# Schematic.net
KiCad netlist of a schematic drawn in Altium Designer
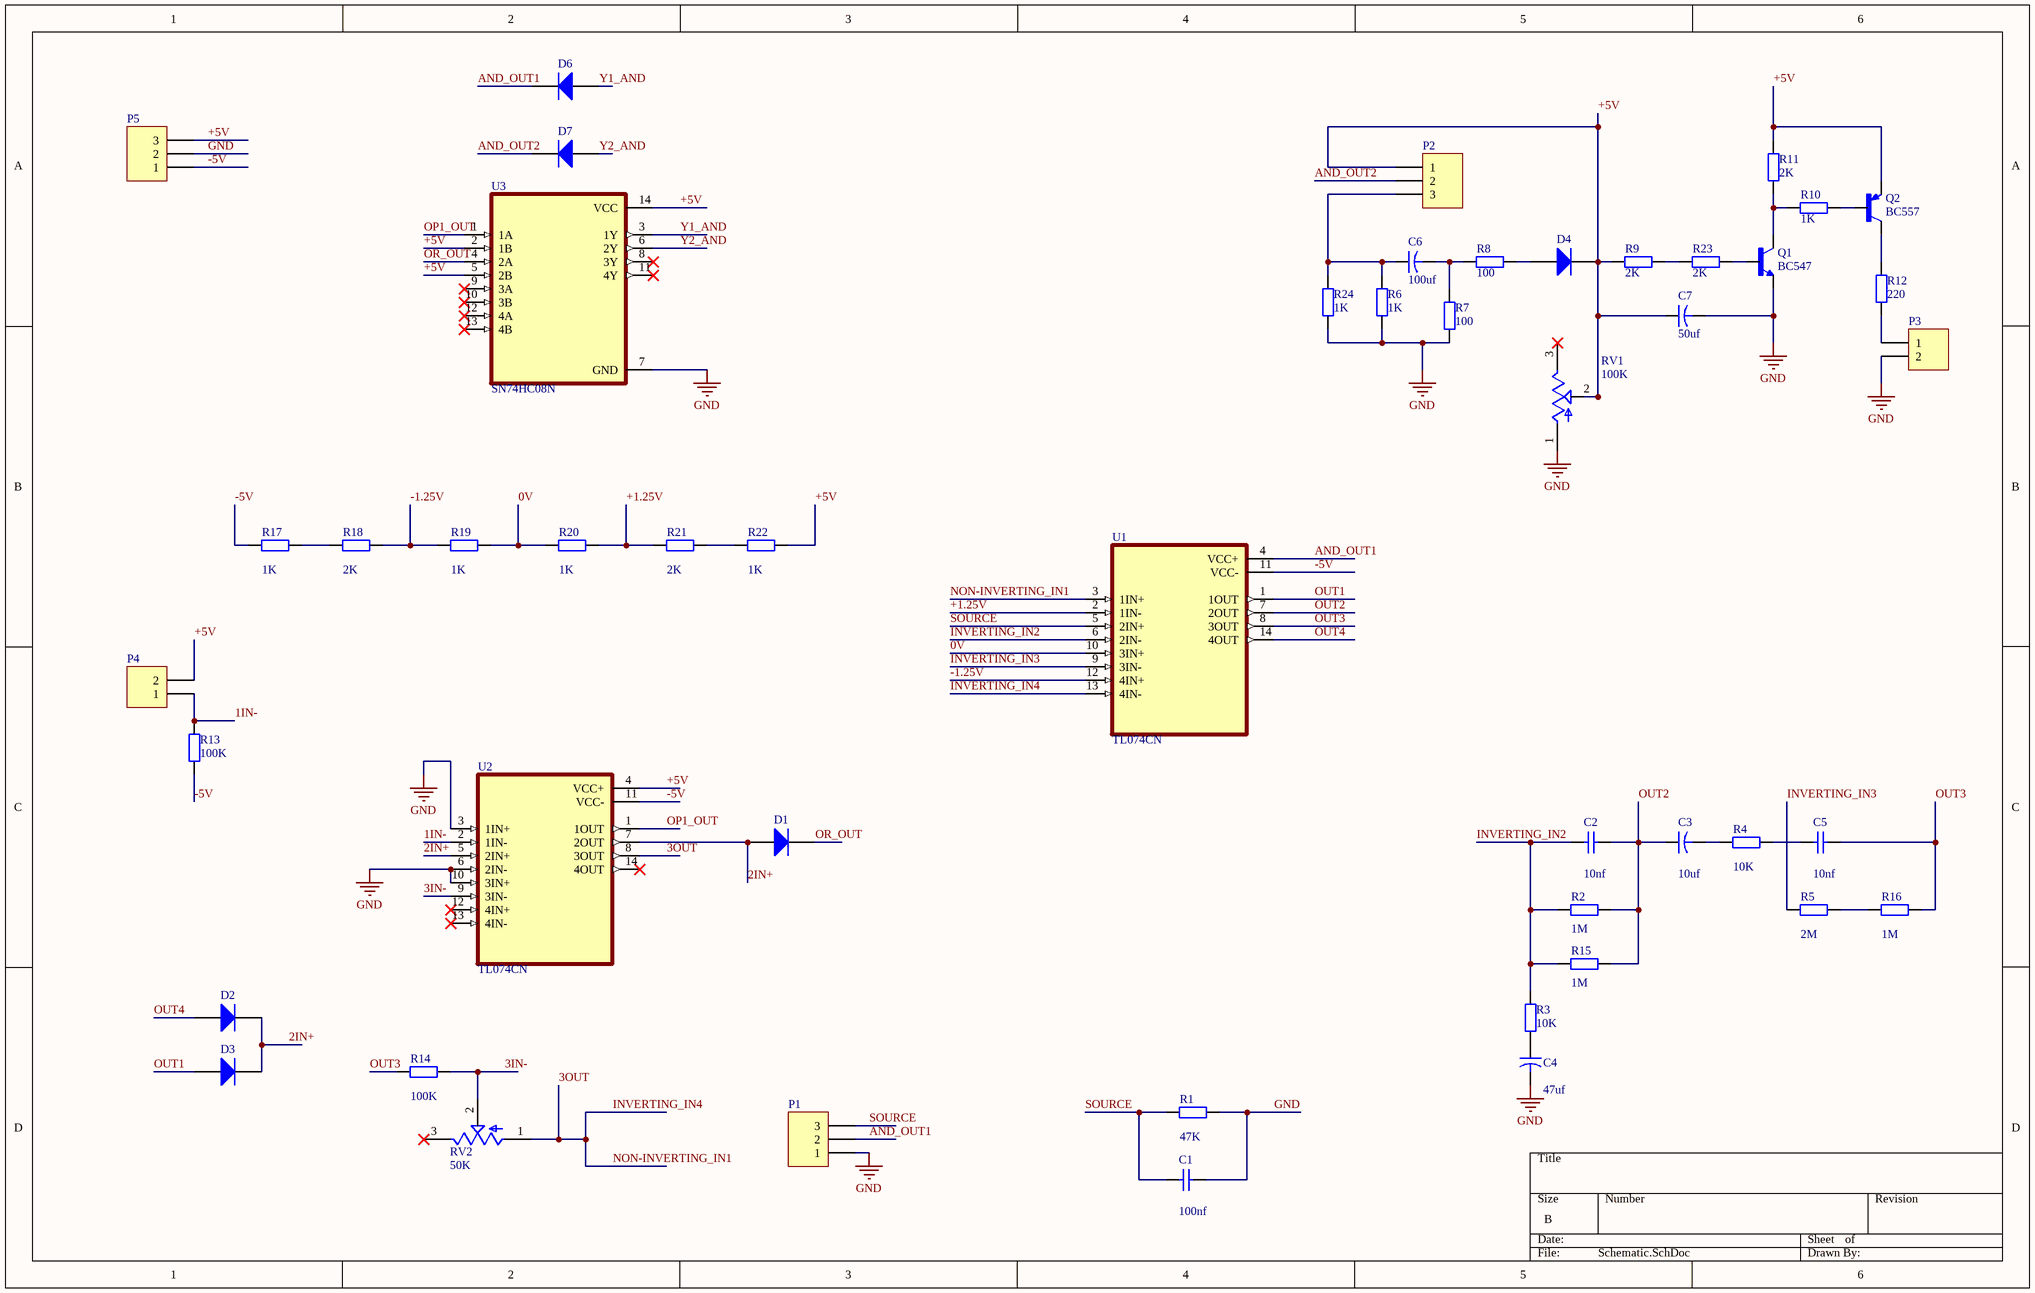
[diagram p0: Schematic.SchDoc]

(export (version "E")
  (design (tool "Eeschema 10.0.6"))
  (components
    (comp (ref "C1")
      (value "100nf")
      (footprint "RAD-0.3")
      (description "Capacitor")
      (fields (field (name "Comment") "Cap") (field (name "PUBLISHER") "Altium Limited"))
      (libsource (lib "Miscellaneous Devices") (part "Cap"))
    )
    (comp (ref "C2")
      (value "10nf")
      (footprint "RAD-0.3")
      (description "Capacitor")
      (fields (field (name "Comment") "Cap") (field (name "PUBLISHER") "Altium Limited"))
      (libsource (lib "Miscellaneous Devices") (part "Cap"))
    )
    (comp (ref "C3")
      (value "10uf")
      (footprint "CAPR5-4X5")
      (description "Capacitor")
      (fields (field (name "Comment") "Cap2") (field (name "PUBLISHER") "Altium Limited"))
      (libsource (lib "Miscellaneous Devices") (part "Cap2"))
    )
    (comp (ref "C4")
      (value "47uf")
      (footprint "CAPR5-4X5")
      (description "Capacitor")
      (fields (field (name "Comment") "Cap2") (field (name "PUBLISHER") "Altium Limited"))
      (libsource (lib "Miscellaneous Devices") (part "Cap2"))
    )
    (comp (ref "C5")
      (value "10nf")
      (footprint "RAD-0.3")
      (description "Capacitor")
      (fields (field (name "Comment") "Cap") (field (name "PUBLISHER") "Altium Limited"))
      (libsource (lib "Miscellaneous Devices") (part "Cap"))
    )
    (comp (ref "C6")
      (value "100uf")
      (footprint "CAPR5-4X5")
      (description "Capacitor")
      (fields (field (name "Comment") "Cap2") (field (name "PUBLISHER") "Altium Limited"))
      (libsource (lib "Miscellaneous Devices") (part "Cap2"))
    )
    (comp (ref "C7")
      (value "50uf")
      (footprint "CAPR5-4X5")
      (description "Capacitor")
      (fields (field (name "Comment") "Cap2") (field (name "PUBLISHER") "Altium Limited"))
      (libsource (lib "Miscellaneous Devices") (part "Cap2"))
    )
    (comp (ref "D1")
      (value "Diode 1N4007")
      (footprint "DO-41")
      (description "1 Amp General Purpose Rectifier")
      (fields (field (name "PUBLISHER") "Altium Limited"))
      (libsource (lib "Miscellaneous Devices") (part "Diode 1N4007"))
    )
    (comp (ref "D2")
      (value "Diode 1N4007")
      (footprint "DO-41")
      (description "1 Amp General Purpose Rectifier")
      (fields (field (name "PUBLISHER") "Altium Limited"))
      (libsource (lib "Miscellaneous Devices") (part "Diode 1N4007"))
    )
    (comp (ref "D3")
      (value "Diode 1N4007")
      (footprint "DO-41")
      (description "1 Amp General Purpose Rectifier")
      (fields (field (name "PUBLISHER") "Altium Limited"))
      (libsource (lib "Miscellaneous Devices") (part "Diode 1N4007"))
    )
    (comp (ref "D4")
      (value "Diode 1N4007")
      (footprint "DO-41")
      (description "1 Amp General Purpose Rectifier")
      (fields (field (name "PUBLISHER") "Altium Limited"))
      (libsource (lib "Miscellaneous Devices") (part "Diode 1N4007"))
    )
    (comp (ref "D6")
      (value "Diode 1N4007")
      (footprint "DO-41")
      (description "1 Amp General Purpose Rectifier")
      (fields (field (name "PUBLISHER") "Altium Limited"))
      (libsource (lib "Miscellaneous Devices") (part "Diode 1N4007"))
    )
    (comp (ref "D7")
      (value "Diode 1N4007")
      (footprint "DO-41")
      (description "1 Amp General Purpose Rectifier")
      (fields (field (name "PUBLISHER") "Altium Limited"))
      (libsource (lib "Miscellaneous Devices") (part "Diode 1N4007"))
    )
    (comp (ref "P1")
      (value "Header 3")
      (footprint "HDR1X3")
      (description "Header, 3-Pin")
      (fields (field (name "PUBLISHER") "Altium Limited"))
      (libsource (lib "Miscellaneous Connectors") (part "Header 3"))
    )
    (comp (ref "P2")
      (value "Header 3")
      (footprint "HDR1X3")
      (description "Header, 3-Pin")
      (fields (field (name "PUBLISHER") "Altium Limited"))
      (libsource (lib "") (part "Header 3_1"))
    )
    (comp (ref "P3")
      (value "Header 2")
      (footprint "HDR1X2")
      (description "Header, 2-Pin")
      (fields (field (name "PUBLISHER") "Altium Limited"))
      (libsource (lib "Miscellaneous Connectors") (part "Header 2"))
    )
    (comp (ref "P4")
      (value "Header 2")
      (footprint "HDR1X2")
      (description "Header, 2-Pin")
      (fields (field (name "PUBLISHER") "Altium Limited"))
      (libsource (lib "") (part "Header 2_1"))
    )
    (comp (ref "P5")
      (value "Header 3")
      (footprint "HDR1X3")
      (description "Header, 3-Pin")
      (fields (field (name "PUBLISHER") "Altium Limited"))
      (libsource (lib "Miscellaneous Connectors") (part "Header 3"))
    )
    (comp (ref "Q1")
      (value "BC547")
      (footprint "TO92260P520H877-3")
      (description "Bipolar _BJT_ Transistor NPN 45V 100mA 300MHz 500mW Through Hole TO-92-3")
      (fields (field (name "MP") "BC547A") (field (name "MF") "ON Semiconductor"))
      (libsource (lib "BC547A") (part "BC547A"))
    )
    (comp (ref "Q2")
      (value "BC557")
      (footprint "TO92260P520H933-3")
      (description "Bipolar (BJT) Transistor PNP 30V 100mA 150MHz 500mW Through Hole TO-92-3")
      (fields (field (name "MP") "BC557AZL1G"))
      (libsource (lib "BC557AZL1G") (part "BC557AZL1G"))
    )
    (comp (ref "R1")
      (value "47K")
      (footprint "AXIAL-0.4")
      (description "Resistor")
      (fields (field (name "Comment") "Res2") (field (name "PUBLISHER") "Altium Limited"))
      (libsource (lib "") (part "Res2_1"))
    )
    (comp (ref "R2")
      (value "1M")
      (footprint "AXIAL-0.4")
      (description "Resistor")
      (fields (field (name "Comment") "Res2") (field (name "PUBLISHER") "Altium Limited"))
      (libsource (lib "") (part "Res2_1"))
    )
    (comp (ref "R3")
      (value "10K")
      (footprint "AXIAL-0.4")
      (description "Resistor")
      (fields (field (name "Comment") "Res2") (field (name "PUBLISHER") "Altium Limited"))
      (libsource (lib "Miscellaneous Devices") (part "Res2"))
    )
    (comp (ref "R4")
      (value "10K")
      (footprint "AXIAL-0.4")
      (description "Resistor")
      (fields (field (name "Comment") "Res2") (field (name "PUBLISHER") "Altium Limited"))
      (libsource (lib "") (part "Res2_1"))
    )
    (comp (ref "R5")
      (value "2M")
      (footprint "AXIAL-0.4")
      (description "Resistor")
      (fields (field (name "Comment") "Res2") (field (name "PUBLISHER") "Altium Limited"))
      (libsource (lib "") (part "Res2_1"))
    )
    (comp (ref "R6")
      (value "1K")
      (footprint "AXIAL-0.4")
      (description "Resistor")
      (fields (field (name "Comment") "Res2") (field (name "PUBLISHER") "Altium Limited"))
      (libsource (lib "Miscellaneous Devices") (part "Res2"))
    )
    (comp (ref "R7")
      (value "100")
      (footprint "AXIAL-0.4")
      (description "Resistor")
      (fields (field (name "Comment") "Res2") (field (name "PUBLISHER") "Altium Limited"))
      (libsource (lib "Miscellaneous Devices") (part "Res2"))
    )
    (comp (ref "R8")
      (value "100")
      (footprint "AXIAL-0.4")
      (description "Resistor")
      (fields (field (name "Comment") "Res2") (field (name "PUBLISHER") "Altium Limited"))
      (libsource (lib "") (part "Res2_2"))
    )
    (comp (ref "R9")
      (value "2K")
      (footprint "AXIAL-0.4")
      (description "Resistor")
      (fields (field (name "Comment") "Res2") (field (name "PUBLISHER") "Altium Limited"))
      (libsource (lib "") (part "Res2_2"))
    )
    (comp (ref "R10")
      (value "1K")
      (footprint "AXIAL-0.4")
      (description "Resistor")
      (fields (field (name "Comment") "Res2") (field (name "PUBLISHER") "Altium Limited"))
      (libsource (lib "") (part "Res2_2"))
    )
    (comp (ref "R11")
      (value "2K")
      (footprint "AXIAL-0.4")
      (description "Resistor")
      (fields (field (name "Comment") "Res2") (field (name "PUBLISHER") "Altium Limited"))
      (libsource (lib "Miscellaneous Devices") (part "Res2"))
    )
    (comp (ref "R12")
      (value "220")
      (footprint "AXIAL-0.4")
      (description "Resistor")
      (fields (field (name "Comment") "Res2") (field (name "PUBLISHER") "Altium Limited"))
      (libsource (lib "Miscellaneous Devices") (part "Res2"))
    )
    (comp (ref "R13")
      (value "100K")
      (footprint "AXIAL-0.4")
      (description "Resistor")
      (fields (field (name "Comment") "Res2") (field (name "PUBLISHER") "Altium Limited"))
      (libsource (lib "Miscellaneous Devices") (part "Res2"))
    )
    (comp (ref "R14")
      (value "100K")
      (footprint "AXIAL-0.4")
      (description "Resistor")
      (fields (field (name "Comment") "Res2") (field (name "PUBLISHER") "Altium Limited"))
      (libsource (lib "") (part "Res2_1"))
    )
    (comp (ref "R15")
      (value "1M")
      (footprint "AXIAL-0.4")
      (description "Resistor")
      (fields (field (name "Comment") "Res2") (field (name "PUBLISHER") "Altium Limited"))
      (libsource (lib "") (part "Res2_1"))
    )
    (comp (ref "R16")
      (value "1M")
      (footprint "AXIAL-0.4")
      (description "Resistor")
      (fields (field (name "Comment") "Res2") (field (name "PUBLISHER") "Altium Limited"))
      (libsource (lib "") (part "Res2_1"))
    )
    (comp (ref "R17")
      (value "1K")
      (footprint "AXIAL-0.4")
      (description "Resistor")
      (fields (field (name "Comment") "Res2") (field (name "PUBLISHER") "Altium Limited"))
      (libsource (lib "") (part "Res2_1"))
    )
    (comp (ref "R18")
      (value "2K")
      (footprint "AXIAL-0.4")
      (description "Resistor")
      (fields (field (name "Comment") "Res2") (field (name "PUBLISHER") "Altium Limited"))
      (libsource (lib "") (part "Res2_1"))
    )
    (comp (ref "R19")
      (value "1K")
      (footprint "AXIAL-0.4")
      (description "Resistor")
      (fields (field (name "Comment") "Res2") (field (name "PUBLISHER") "Altium Limited"))
      (libsource (lib "") (part "Res2_1"))
    )
    (comp (ref "R20")
      (value "1K")
      (footprint "AXIAL-0.4")
      (description "Resistor")
      (fields (field (name "Comment") "Res2") (field (name "PUBLISHER") "Altium Limited"))
      (libsource (lib "") (part "Res2_1"))
    )
    (comp (ref "R21")
      (value "2K")
      (footprint "AXIAL-0.4")
      (description "Resistor")
      (fields (field (name "Comment") "Res2") (field (name "PUBLISHER") "Altium Limited"))
      (libsource (lib "") (part "Res2_1"))
    )
    (comp (ref "R22")
      (value "1K")
      (footprint "AXIAL-0.4")
      (description "Resistor")
      (fields (field (name "Comment") "Res2") (field (name "PUBLISHER") "Altium Limited"))
      (libsource (lib "") (part "Res2_1"))
    )
    (comp (ref "R23")
      (value "2K")
      (footprint "AXIAL-0.4")
      (description "Resistor")
      (fields (field (name "Comment") "Res2") (field (name "PUBLISHER") "Altium Limited"))
      (libsource (lib "") (part "Res2_2"))
    )
    (comp (ref "R24")
      (value "1K")
      (footprint "AXIAL-0.4")
      (description "Resistor")
      (fields (field (name "Comment") "Res2") (field (name "PUBLISHER") "Altium Limited"))
      (libsource (lib "Miscellaneous Devices") (part "Res2"))
    )
    (comp (ref "RV1")
      (value "100K")
      (footprint "TRIM_3362P-1-501")
      (fields (field (name "MP") "3362P-1-501") (field (name "MF") "Bourns"))
      (libsource (lib "3362P-1-501") (part "3362P-1-501"))
    )
    (comp (ref "RV2")
      (value "50K")
      (footprint "TRIM_3362P-1-501")
      (fields (field (name "MP") "3362P-1-501") (field (name "MF") "Bourns"))
      (libsource (lib "3362P-1-501") (part "3362P-1-501"))
    )
    (comp (ref "U1")
      (value "TL074CN")
      (footprint "DIP794W45P254L1969H508Q14")
      (description "Quad Low-Noise JFET-Input General-Purpose Operational Amplifier 14-PDIP 0 to 70")
      (fields (field (name "MF") "Texas Instruments"))
      (libsource (lib "TL074CN") (part "TL074CN"))
    )
    (comp (ref "U2")
      (value "TL074CN")
      (footprint "DIP794W45P254L1969H508Q14")
      (description "Quad Low-Noise JFET-Input General-Purpose Operational Amplifier 14-PDIP 0 to 70")
      (fields (field (name "MF") "Texas Instruments"))
      (libsource (lib "TL074CN") (part "TL074CN"))
    )
    (comp (ref "U3")
      (value "SN74HC08N")
      (footprint "DIP794W45P254L1969H508Q14")
      (description "Quadruple 2-input positive-AND gates 14-PDIP -40 to 85")
      (fields
        (field (name "MF") "Texas Instruments")
        (field (name "BUYPART") "https://www.snapeda.com/parts/SN74HC08N/Texas%20Instruments/view-part/2878259/?ref=eda")
      )
      (libsource (lib "SN74HC08N") (part "SN74HC08N"))
    )
  )
  (nets
    (net (code "1") (name "/+1.25V") (class "Default")
      (node (ref "R20") (pin "2") (pinfunction "2_2") (pintype "passive"))
      (node (ref "R21") (pin "1") (pinfunction "1_1") (pintype "passive"))
      (node (ref "U1") (pin "2") (pinfunction "1IN-_2") (pintype "input"))
    )
    (net (code "2") (name "/+5V") (class "Default")
      (node (ref "C7") (pin "1") (pinfunction "1_1") (pintype "passive"))
      (node (ref "D4") (pin "2") (pinfunction "K_2") (pintype "passive"))
      (node (ref "P2") (pin "1") (pinfunction "1_1") (pintype "passive"))
      (node (ref "P4") (pin "2") (pinfunction "2_2") (pintype "passive"))
      (node (ref "P5") (pin "3") (pinfunction "3_3") (pintype "passive"))
      (node (ref "Q2") (pin "3") (pinfunction "E_3") (pintype "passive"))
      (node (ref "R11") (pin "2") (pinfunction "2_2") (pintype "passive"))
      (node (ref "R22") (pin "2") (pinfunction "2_2") (pintype "passive"))
      (node (ref "R9") (pin "2") (pinfunction "2_2") (pintype "passive"))
      (node (ref "RV1") (pin "2") (pinfunction "WIPER_2") (pintype "passive"))
      (node (ref "U2") (pin "4") (pinfunction "VCC+_4") (pintype "power_in"))
      (node (ref "U3") (pin "14") (pinfunction "VCC_14") (pintype "power_in"))
      (node (ref "U3") (pin "2") (pinfunction "1B_2") (pintype "input"))
      (node (ref "U3") (pin "5") (pinfunction "2B_5") (pintype "input"))
    )
    (net (code "3") (name "/-1.25V") (class "Default")
      (node (ref "R18") (pin "2") (pinfunction "2_2") (pintype "passive"))
      (node (ref "R19") (pin "1") (pinfunction "1_1") (pintype "passive"))
      (node (ref "U1") (pin "12") (pinfunction "4IN+_12") (pintype "input"))
    )
    (net (code "4") (name "/-5V") (class "Default")
      (node (ref "P5") (pin "1") (pinfunction "1_1") (pintype "passive"))
      (node (ref "R13") (pin "1") (pinfunction "1_1") (pintype "passive"))
      (node (ref "R17") (pin "1") (pinfunction "1_1") (pintype "passive"))
      (node (ref "U1") (pin "11") (pinfunction "VCC-_11") (pintype "power_in"))
      (node (ref "U2") (pin "11") (pinfunction "VCC-_11") (pintype "power_in"))
    )
    (net (code "5") (name "/0V") (class "Default")
      (node (ref "R19") (pin "2") (pinfunction "2_2") (pintype "passive"))
      (node (ref "R20") (pin "1") (pinfunction "1_1") (pintype "passive"))
      (node (ref "U1") (pin "10") (pinfunction "3IN+_10") (pintype "input"))
    )
    (net (code "6") (name "/1IN-") (class "Default")
      (node (ref "P4") (pin "1") (pinfunction "1_1") (pintype "passive"))
      (node (ref "R13") (pin "2") (pinfunction "2_2") (pintype "passive"))
      (node (ref "U2") (pin "2") (pinfunction "1IN-_2") (pintype "input"))
    )
    (net (code "7") (name "/2IN+") (class "Default")
      (node (ref "D1") (pin "1") (pinfunction "A_1") (pintype "passive"))
      (node (ref "D2") (pin "2") (pinfunction "K_2") (pintype "passive"))
      (node (ref "D3") (pin "2") (pinfunction "K_2") (pintype "passive"))
      (node (ref "U2") (pin "5") (pinfunction "2IN+_5") (pintype "input"))
      (node (ref "U2") (pin "7") (pinfunction "2OUT_7") (pintype "output"))
    )
    (net (code "8") (name "/3IN-") (class "Default")
      (node (ref "R14") (pin "2") (pinfunction "2_2") (pintype "passive"))
      (node (ref "RV2") (pin "2") (pinfunction "WIPER_2") (pintype "passive"))
      (node (ref "U2") (pin "9") (pinfunction "3IN-_9") (pintype "input"))
    )
    (net (code "9") (name "/3OUT") (class "Default")
      (node (ref "RV2") (pin "1") (pinfunction "CCW_1") (pintype "passive"))
      (node (ref "U1") (pin "13") (pinfunction "4IN-_13") (pintype "input"))
      (node (ref "U1") (pin "3") (pinfunction "1IN+_3") (pintype "input"))
      (node (ref "U2") (pin "8") (pinfunction "3OUT_8") (pintype "output"))
    )
    (net (code "10") (name "/AND_OUT1") (class "Default")
      (node (ref "D6") (pin "2") (pinfunction "K_2") (pintype "passive"))
      (node (ref "P1") (pin "2") (pinfunction "2_2") (pintype "passive"))
      (node (ref "U1") (pin "4") (pinfunction "VCC+_4") (pintype "power_in"))
    )
    (net (code "11") (name "/AND_OUT2") (class "Default")
      (node (ref "D7") (pin "2") (pinfunction "K_2") (pintype "passive"))
      (node (ref "P2") (pin "2") (pinfunction "2_2") (pintype "passive"))
    )
    (net (code "12") (name "/INVERTING_IN2") (class "Default")
      (node (ref "C2") (pin "1") (pinfunction "1_1") (pintype "passive"))
      (node (ref "R15") (pin "1") (pinfunction "1_1") (pintype "passive"))
      (node (ref "R2") (pin "1") (pinfunction "1_1") (pintype "passive"))
      (node (ref "R3") (pin "2") (pinfunction "2_2") (pintype "passive"))
      (node (ref "U1") (pin "6") (pinfunction "2IN-_6") (pintype "input"))
    )
    (net (code "13") (name "/INVERTING_IN3") (class "Default")
      (node (ref "R5") (pin "1") (pinfunction "1_1") (pintype "passive"))
      (node (ref "U1") (pin "9") (pinfunction "3IN-_9") (pintype "input"))
    )
    (net (code "14") (name "/OP1_OUT") (class "Default")
      (node (ref "U2") (pin "1") (pinfunction "1OUT_1") (pintype "output"))
      (node (ref "U3") (pin "1") (pinfunction "1A_1") (pintype "input"))
    )
    (net (code "15") (name "/OR_OUT") (class "Default")
      (node (ref "D1") (pin "2") (pinfunction "K_2") (pintype "passive"))
      (node (ref "U3") (pin "4") (pinfunction "2A_4") (pintype "input"))
    )
    (net (code "16") (name "/OUT1") (class "Default")
      (node (ref "D3") (pin "1") (pinfunction "A_1") (pintype "passive"))
      (node (ref "U1") (pin "1") (pinfunction "1OUT_1") (pintype "output"))
    )
    (net (code "17") (name "/OUT2") (class "Default")
      (node (ref "C2") (pin "2") (pinfunction "2_2") (pintype "passive"))
      (node (ref "C3") (pin "1") (pinfunction "1_1") (pintype "passive"))
      (node (ref "R15") (pin "2") (pinfunction "2_2") (pintype "passive"))
      (node (ref "R2") (pin "2") (pinfunction "2_2") (pintype "passive"))
      (node (ref "U1") (pin "7") (pinfunction "2OUT_7") (pintype "output"))
    )
    (net (code "18") (name "/OUT3") (class "Default")
      (node (ref "C5") (pin "2") (pinfunction "2_2") (pintype "passive"))
      (node (ref "R14") (pin "1") (pinfunction "1_1") (pintype "passive"))
      (node (ref "R16") (pin "2") (pinfunction "2_2") (pintype "passive"))
      (node (ref "U1") (pin "8") (pinfunction "3OUT_8") (pintype "output"))
    )
    (net (code "19") (name "/OUT4") (class "Default")
      (node (ref "D2") (pin "1") (pinfunction "A_1") (pintype "passive"))
      (node (ref "U1") (pin "14") (pinfunction "4OUT_14") (pintype "output"))
    )
    (net (code "20") (name "/SOURCE") (class "Default")
      (node (ref "C1") (pin "1") (pinfunction "1_1") (pintype "passive"))
      (node (ref "P1") (pin "3") (pinfunction "3_3") (pintype "passive"))
      (node (ref "R1") (pin "1") (pinfunction "1_1") (pintype "passive"))
      (node (ref "U1") (pin "5") (pinfunction "2IN+_5") (pintype "input"))
    )
    (net (code "21") (name "/Y1_AND") (class "Default")
      (node (ref "D6") (pin "1") (pinfunction "A_1") (pintype "passive"))
      (node (ref "U3") (pin "3") (pinfunction "1Y_3") (pintype "output"))
    )
    (net (code "22") (name "/Y2_AND") (class "Default")
      (node (ref "D7") (pin "1") (pinfunction "A_1") (pintype "passive"))
      (node (ref "U3") (pin "6") (pinfunction "2Y_6") (pintype "output"))
    )
    (net (code "23") (name "GND") (class "Default")
      (node (ref "C1") (pin "2") (pinfunction "2_2") (pintype "passive"))
      (node (ref "C4") (pin "2") (pinfunction "2_2") (pintype "passive"))
      (node (ref "C7") (pin "2") (pinfunction "2_2") (pintype "passive"))
      (node (ref "P1") (pin "1") (pinfunction "1_1") (pintype "passive"))
      (node (ref "P3") (pin "2") (pinfunction "2_2") (pintype "passive"))
      (node (ref "P5") (pin "2") (pinfunction "2_2") (pintype "passive"))
      (node (ref "Q1") (pin "3") (pinfunction "E_3") (pintype "passive"))
      (node (ref "R1") (pin "2") (pinfunction "2_2") (pintype "passive"))
      (node (ref "R24") (pin "1") (pinfunction "1_1") (pintype "passive"))
      (node (ref "R6") (pin "1") (pinfunction "1_1") (pintype "passive"))
      (node (ref "R7") (pin "1") (pinfunction "1_1") (pintype "passive"))
      (node (ref "RV1") (pin "1") (pinfunction "CCW_1") (pintype "passive"))
      (node (ref "U2") (pin "10") (pinfunction "3IN+_10") (pintype "input"))
      (node (ref "U2") (pin "3") (pinfunction "1IN+_3") (pintype "input"))
      (node (ref "U2") (pin "6") (pinfunction "2IN-_6") (pintype "input"))
      (node (ref "U3") (pin "7") (pinfunction "GND_7") (pintype "power_in"))
    )
    (net (code "24") (name "Net-(C3-Pad2)") (class "Default")
      (node (ref "C3") (pin "2") (pinfunction "2_2") (pintype "passive"))
      (node (ref "R4") (pin "1") (pinfunction "1_1") (pintype "passive"))
    )
    (net (code "25") (name "Net-(C4-Pad1)") (class "Default")
      (node (ref "C4") (pin "1") (pinfunction "1_1") (pintype "passive"))
      (node (ref "R3") (pin "1") (pinfunction "1_1") (pintype "passive"))
    )
    (net (code "26") (name "Net-(C5-Pad1)") (class "Default")
      (node (ref "C5") (pin "1") (pinfunction "1_1") (pintype "passive"))
      (node (ref "R4") (pin "2") (pinfunction "2_2") (pintype "passive"))
    )
    (net (code "27") (name "Net-(C6-Pad1)") (class "Default")
      (node (ref "C6") (pin "1") (pinfunction "1_1") (pintype "passive"))
      (node (ref "P2") (pin "3") (pinfunction "3_3") (pintype "passive"))
      (node (ref "R24") (pin "2") (pinfunction "2_2") (pintype "passive"))
      (node (ref "R6") (pin "2") (pinfunction "2_2") (pintype "passive"))
    )
    (net (code "28") (name "Net-(C6-Pad2)") (class "Default")
      (node (ref "C6") (pin "2") (pinfunction "2_2") (pintype "passive"))
      (node (ref "R7") (pin "2") (pinfunction "2_2") (pintype "passive"))
      (node (ref "R8") (pin "2") (pinfunction "2_2") (pintype "passive"))
    )
    (net (code "29") (name "Net-(D4-A)") (class "Default")
      (node (ref "D4") (pin "1") (pinfunction "A_1") (pintype "passive"))
      (node (ref "R8") (pin "1") (pinfunction "1_1") (pintype "passive"))
    )
    (net (code "30") (name "Net-(P3-Pad1)") (class "Default")
      (node (ref "P3") (pin "1") (pinfunction "1_1") (pintype "passive"))
      (node (ref "R12") (pin "1") (pinfunction "1_1") (pintype "passive"))
    )
    (net (code "31") (name "Net-(Q1-B)") (class "Default")
      (node (ref "Q1") (pin "2") (pinfunction "B_2") (pintype "passive"))
      (node (ref "R23") (pin "1") (pinfunction "1_1") (pintype "passive"))
    )
    (net (code "32") (name "Net-(Q1-C)") (class "Default")
      (node (ref "Q1") (pin "1") (pinfunction "C_1") (pintype "passive"))
      (node (ref "R10") (pin "2") (pinfunction "2_2") (pintype "passive"))
      (node (ref "R11") (pin "1") (pinfunction "1_1") (pintype "passive"))
    )
    (net (code "33") (name "Net-(Q2-B)") (class "Default")
      (node (ref "Q2") (pin "2") (pinfunction "B_2") (pintype "passive"))
      (node (ref "R10") (pin "1") (pinfunction "1_1") (pintype "passive"))
    )
    (net (code "34") (name "Net-(Q2-C)") (class "Default")
      (node (ref "Q2") (pin "1") (pinfunction "C_1") (pintype "passive"))
      (node (ref "R12") (pin "2") (pinfunction "2_2") (pintype "passive"))
    )
    (net (code "35") (name "Net-(R16-Pad1)") (class "Default")
      (node (ref "R16") (pin "1") (pinfunction "1_1") (pintype "passive"))
      (node (ref "R5") (pin "2") (pinfunction "2_2") (pintype "passive"))
    )
    (net (code "36") (name "Net-(R17-Pad2)") (class "Default")
      (node (ref "R17") (pin "2") (pinfunction "2_2") (pintype "passive"))
      (node (ref "R18") (pin "1") (pinfunction "1_1") (pintype "passive"))
    )
    (net (code "37") (name "Net-(R21-Pad2)") (class "Default")
      (node (ref "R21") (pin "2") (pinfunction "2_2") (pintype "passive"))
      (node (ref "R22") (pin "1") (pinfunction "1_1") (pintype "passive"))
    )
    (net (code "38") (name "Net-(R23-Pad2)") (class "Default")
      (node (ref "R23") (pin "2") (pinfunction "2_2") (pintype "passive"))
      (node (ref "R9") (pin "1") (pinfunction "1_1") (pintype "passive"))
    )
    (net (code "39") (name "unconnected-(RV1-CW-Pad3)") (class "Default")
      (node (ref "RV1") (pin "3") (pinfunction "CW_3") (pintype "passive+no_connect"))
    )
    (net (code "40") (name "unconnected-(RV2-CW-Pad3)") (class "Default")
      (node (ref "RV2") (pin "3") (pinfunction "CW_3") (pintype "passive+no_connect"))
    )
    (net (code "41") (name "unconnected-(U2-4IN+-Pad12)") (class "Default")
      (node (ref "U2") (pin "12") (pinfunction "4IN+_12") (pintype "input+no_connect"))
    )
    (net (code "42") (name "unconnected-(U2-4IN--Pad13)") (class "Default")
      (node (ref "U2") (pin "13") (pinfunction "4IN-_13") (pintype "input+no_connect"))
    )
    (net (code "43") (name "unconnected-(U2-4OUT-Pad14)") (class "Default")
      (node (ref "U2") (pin "14") (pinfunction "4OUT_14") (pintype "output+no_connect"))
    )
    (net (code "44") (name "unconnected-(U3-3A-Pad9)") (class "Default")
      (node (ref "U3") (pin "9") (pinfunction "3A_9") (pintype "input+no_connect"))
    )
    (net (code "45") (name "unconnected-(U3-3B-Pad10)") (class "Default")
      (node (ref "U3") (pin "10") (pinfunction "3B_10") (pintype "input+no_connect"))
    )
    (net (code "46") (name "unconnected-(U3-3Y-Pad8)") (class "Default")
      (node (ref "U3") (pin "8") (pinfunction "3Y_8") (pintype "output+no_connect"))
    )
    (net (code "47") (name "unconnected-(U3-4A-Pad12)") (class "Default")
      (node (ref "U3") (pin "12") (pinfunction "4A_12") (pintype "input+no_connect"))
    )
    (net (code "48") (name "unconnected-(U3-4B-Pad13)") (class "Default")
      (node (ref "U3") (pin "13") (pinfunction "4B_13") (pintype "input+no_connect"))
    )
    (net (code "49") (name "unconnected-(U3-4Y-Pad11)") (class "Default")
      (node (ref "U3") (pin "11") (pinfunction "4Y_11") (pintype "output+no_connect"))
    )
  )
)
